# ADC.net
KiCad netlist of a schematic drawn in Altium Designer
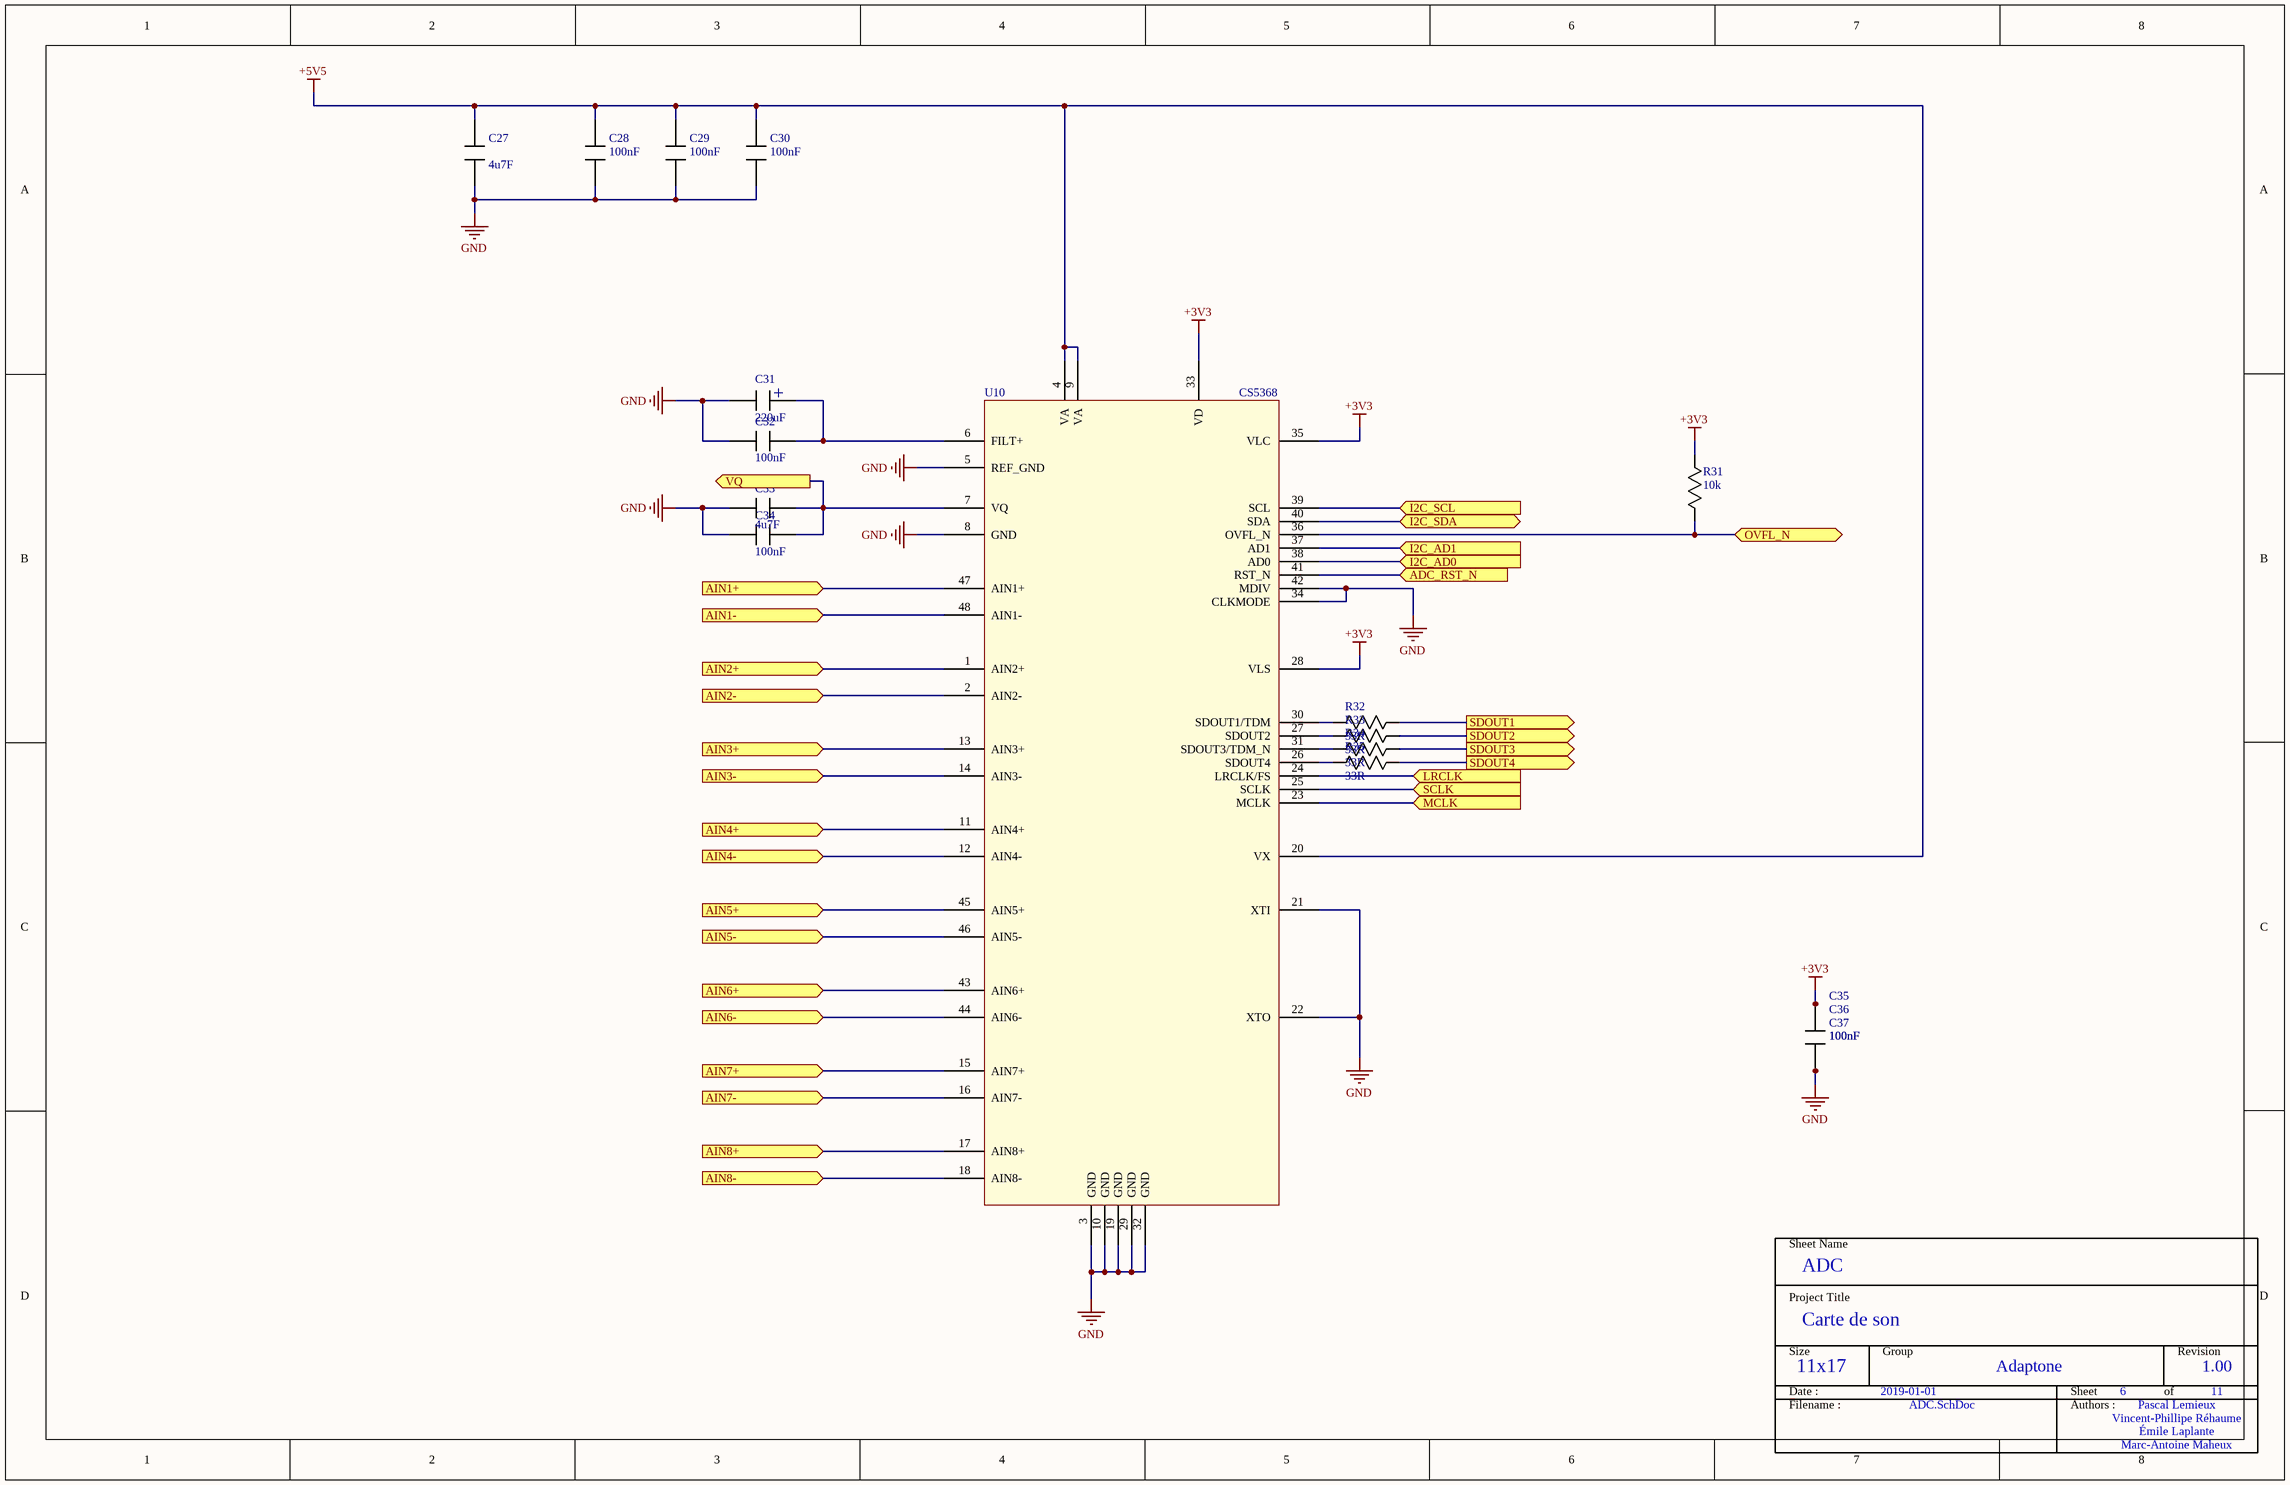
[diagram p0: ADC.SchDoc]

(export (version "E")
  (design (tool "Eeschema 10.0.6"))
  (components
    (comp (ref "C27")
      (value "4u7F")
      (footprint "0805")
      (description "Capacitor")
      (fields (field (name "MFG") "Samsung"))
      (libsource (lib "ADAPTONE_CARTE_DE_SON") (part "Capacitor"))
    )
    (comp (ref "C28")
      (value "100nF")
      (footprint "0603")
      (description "Capacitor")
      (fields (field (name "MFG") "Samsung"))
      (libsource (lib "ADAPTONE_CARTE_DE_SON") (part "Capacitor"))
    )
    (comp (ref "C29")
      (value "100nF")
      (footprint "0603")
      (description "Capacitor")
      (fields (field (name "MFG") "Samsung"))
      (libsource (lib "ADAPTONE_CARTE_DE_SON") (part "Capacitor"))
    )
    (comp (ref "C30")
      (value "100nF")
      (footprint "0603")
      (description "Capacitor")
      (fields (field (name "MFG") "Samsung"))
      (libsource (lib "ADAPTONE_CARTE_DE_SON") (part "Capacitor"))
    )
    (comp (ref "C31")
      (value "220uF")
      (footprint "CAP_RAD_SMD_DIA315")
      (description "Capacitor")
      (fields (field (name "MFG") "Nichicon") (field (name "Comment") "Capacitor_Polarized_1"))
      (libsource (lib "ADAPTONE_CARTE_DE_SON") (part "Capacitor_Polarized_1"))
    )
    (comp (ref "C32")
      (value "100nF")
      (footprint "0603")
      (description "Capacitor")
      (fields (field (name "MFG") "Samsung"))
      (libsource (lib "ADAPTONE_CARTE_DE_SON") (part "Capacitor"))
    )
    (comp (ref "C33")
      (value "4u7F")
      (footprint "0805")
      (description "Capacitor")
      (fields (field (name "MFG") "Samsung"))
      (libsource (lib "ADAPTONE_CARTE_DE_SON") (part "Capacitor"))
    )
    (comp (ref "C34")
      (value "100nF")
      (footprint "0603")
      (description "Capacitor")
      (fields (field (name "MFG") "Samsung"))
      (libsource (lib "ADAPTONE_CARTE_DE_SON") (part "Capacitor"))
    )
    (comp (ref "C35")
      (value "100nF")
      (footprint "0603")
      (description "Capacitor")
      (fields (field (name "MFG") "Samsung"))
      (libsource (lib "ADAPTONE_CARTE_DE_SON") (part "Capacitor"))
    )
    (comp (ref "C36")
      (value "100nF")
      (footprint "0603")
      (description "Capacitor")
      (fields (field (name "MFG") "Samsung"))
      (libsource (lib "ADAPTONE_CARTE_DE_SON") (part "Capacitor"))
    )
    (comp (ref "C37")
      (value "100nF")
      (footprint "0603")
      (description "Capacitor")
      (fields (field (name "MFG") "Samsung"))
      (libsource (lib "ADAPTONE_CARTE_DE_SON") (part "Capacitor"))
    )
    (comp (ref "R31")
      (value "10k")
      (footprint "0603")
      (description "Resistor")
      (fields (field (name "MFG") "Yageo"))
      (libsource (lib "ADAPTONE_CARTE_DE_SON") (part "Resistor"))
    )
    (comp (ref "R32")
      (value "33R")
      (footprint "0603")
      (description "Resistor")
      (fields (field (name "MFG") "Yageo"))
      (libsource (lib "ADAPTONE_CARTE_DE_SON") (part "Resistor"))
    )
    (comp (ref "R33")
      (value "33R")
      (footprint "0603")
      (description "Resistor")
      (fields (field (name "MFG") "Yageo"))
      (libsource (lib "ADAPTONE_CARTE_DE_SON") (part "Resistor"))
    )
    (comp (ref "R34")
      (value "33R")
      (footprint "0603")
      (description "Resistor")
      (fields (field (name "MFG") "Yageo"))
      (libsource (lib "ADAPTONE_CARTE_DE_SON") (part "Resistor"))
    )
    (comp (ref "R35")
      (value "33R")
      (footprint "0603")
      (description "Resistor")
      (fields (field (name "MFG") "Yageo"))
      (libsource (lib "ADAPTONE_CARTE_DE_SON") (part "Resistor"))
    )
    (comp (ref "U10")
      (value "CS5368")
      (footprint "LQFP_48L_CIRRUS")
      (description "ADC, 24bit, 8 chan, 192kHz, PCM, TDM, LQFP48")
      (fields (field (name "MFG") "Cirrus"))
      (libsource (lib "ADAPTONE_CARTE_DE_SON") (part "CS5368"))
    )
  )
  (nets
    (net (code "1") (name "+3V3") (class "Default")
      (node (ref "C35") (pin "1") (pintype "passive"))
      (node (ref "C36") (pin "1") (pintype "passive"))
      (node (ref "C37") (pin "1") (pintype "passive"))
      (node (ref "R31") (pin "1") (pintype "passive"))
      (node (ref "U10") (pin "28") (pinfunction "VLS_28") (pintype "passive"))
      (node (ref "U10") (pin "33") (pinfunction "VD_33") (pintype "passive"))
      (node (ref "U10") (pin "35") (pinfunction "VLC_35") (pintype "passive"))
    )
    (net (code "2") (name "+5V5") (class "Default")
      (node (ref "C27") (pin "1") (pintype "passive"))
      (node (ref "C28") (pin "1") (pintype "passive"))
      (node (ref "C29") (pin "1") (pintype "passive"))
      (node (ref "C30") (pin "1") (pintype "passive"))
      (node (ref "U10") (pin "20") (pinfunction "VX_20") (pintype "passive"))
      (node (ref "U10") (pin "4") (pinfunction "VA_4") (pintype "passive"))
      (node (ref "U10") (pin "9") (pinfunction "VA_9") (pintype "passive"))
    )
    (net (code "3") (name "/ADC_RST_N") (class "Default")
      (node (ref "U10") (pin "41") (pinfunction "RST_N_41") (pintype "passive"))
    )
    (net (code "4") (name "/AIN1+") (class "Default")
      (node (ref "U10") (pin "47") (pinfunction "AIN1+_47") (pintype "passive"))
    )
    (net (code "5") (name "/AIN1-") (class "Default")
      (node (ref "U10") (pin "48") (pinfunction "AIN1-_48") (pintype "passive"))
    )
    (net (code "6") (name "/AIN2+") (class "Default")
      (node (ref "U10") (pin "1") (pinfunction "AIN2+_1") (pintype "passive"))
    )
    (net (code "7") (name "/AIN2-") (class "Default")
      (node (ref "U10") (pin "2") (pinfunction "AIN2-_2") (pintype "passive"))
    )
    (net (code "8") (name "/AIN3+") (class "Default")
      (node (ref "U10") (pin "13") (pinfunction "AIN3+_13") (pintype "passive"))
    )
    (net (code "9") (name "/AIN3-") (class "Default")
      (node (ref "U10") (pin "14") (pinfunction "AIN3-_14") (pintype "passive"))
    )
    (net (code "10") (name "/AIN4+") (class "Default")
      (node (ref "U10") (pin "11") (pinfunction "AIN4+_11") (pintype "passive"))
    )
    (net (code "11") (name "/AIN4-") (class "Default")
      (node (ref "U10") (pin "12") (pinfunction "AIN4-_12") (pintype "passive"))
    )
    (net (code "12") (name "/AIN5+") (class "Default")
      (node (ref "U10") (pin "45") (pinfunction "AIN5+_45") (pintype "passive"))
    )
    (net (code "13") (name "/AIN5-") (class "Default")
      (node (ref "U10") (pin "46") (pinfunction "AIN5-_46") (pintype "passive"))
    )
    (net (code "14") (name "/AIN6+") (class "Default")
      (node (ref "U10") (pin "43") (pinfunction "AIN6+_43") (pintype "passive"))
    )
    (net (code "15") (name "/AIN6-") (class "Default")
      (node (ref "U10") (pin "44") (pinfunction "AIN6-_44") (pintype "passive"))
    )
    (net (code "16") (name "/AIN7+") (class "Default")
      (node (ref "U10") (pin "15") (pinfunction "AIN7+_15") (pintype "passive"))
    )
    (net (code "17") (name "/AIN7-") (class "Default")
      (node (ref "U10") (pin "16") (pinfunction "AIN7-_16") (pintype "passive"))
    )
    (net (code "18") (name "/AIN8+") (class "Default")
      (node (ref "U10") (pin "17") (pinfunction "AIN8+_17") (pintype "passive"))
    )
    (net (code "19") (name "/AIN8-") (class "Default")
      (node (ref "U10") (pin "18") (pinfunction "AIN8-_18") (pintype "passive"))
    )
    (net (code "20") (name "/I2C_AD0") (class "Default")
      (node (ref "U10") (pin "38") (pinfunction "AD0_38") (pintype "passive"))
    )
    (net (code "21") (name "/I2C_AD1") (class "Default")
      (node (ref "U10") (pin "37") (pinfunction "AD1_37") (pintype "passive"))
    )
    (net (code "22") (name "/I2C_SCL") (class "Default")
      (node (ref "U10") (pin "39") (pinfunction "SCL_39") (pintype "passive"))
    )
    (net (code "23") (name "/I2C_SDA") (class "Default")
      (node (ref "U10") (pin "40") (pinfunction "SDA_40") (pintype "passive"))
    )
    (net (code "24") (name "/LRCLK") (class "Default")
      (node (ref "U10") (pin "24") (pinfunction "LRCLK/FS_24") (pintype "passive"))
    )
    (net (code "25") (name "/MCLK") (class "Default")
      (node (ref "U10") (pin "23") (pinfunction "MCLK_23") (pintype "passive"))
    )
    (net (code "26") (name "/OVFL_N") (class "Default")
      (node (ref "R31") (pin "2") (pintype "passive"))
      (node (ref "U10") (pin "36") (pinfunction "OVFL_N_36") (pintype "passive"))
    )
    (net (code "27") (name "/SCLK") (class "Default")
      (node (ref "U10") (pin "25") (pinfunction "SCLK_25") (pintype "passive"))
    )
    (net (code "28") (name "/SDOUT1") (class "Default") (node (ref "R32") (pin "2") (pintype "passive")))
    (net (code "29") (name "/SDOUT2") (class "Default") (node (ref "R33") (pin "2") (pintype "passive")))
    (net (code "30") (name "/SDOUT3") (class "Default") (node (ref "R34") (pin "2") (pintype "passive")))
    (net (code "31") (name "/SDOUT4") (class "Default") (node (ref "R35") (pin "2") (pintype "passive")))
    (net (code "32") (name "/VQ") (class "Default")
      (node (ref "C33") (pin "1") (pintype "passive"))
      (node (ref "C34") (pin "1") (pintype "passive"))
      (node (ref "U10") (pin "7") (pinfunction "VQ_7") (pintype "passive"))
    )
    (net (code "33") (name "GND") (class "Default")
      (node (ref "C27") (pin "2") (pintype "passive"))
      (node (ref "C28") (pin "2") (pintype "passive"))
      (node (ref "C29") (pin "2") (pintype "passive"))
      (node (ref "C30") (pin "2") (pintype "passive"))
      (node (ref "C31") (pin "-") (pintype "passive"))
      (node (ref "C32") (pin "2") (pintype "passive"))
      (node (ref "C33") (pin "2") (pintype "passive"))
      (node (ref "C34") (pin "2") (pintype "passive"))
      (node (ref "C35") (pin "2") (pintype "passive"))
      (node (ref "C36") (pin "2") (pintype "passive"))
      (node (ref "C37") (pin "2") (pintype "passive"))
      (node (ref "U10") (pin "10") (pinfunction "GND_10") (pintype "passive"))
      (node (ref "U10") (pin "19") (pinfunction "GND_19") (pintype "passive"))
      (node (ref "U10") (pin "21") (pinfunction "XTI_21") (pintype "passive"))
      (node (ref "U10") (pin "22") (pinfunction "XTO_22") (pintype "passive"))
      (node (ref "U10") (pin "29") (pinfunction "GND_29") (pintype "passive"))
      (node (ref "U10") (pin "3") (pinfunction "GND_3") (pintype "passive"))
      (node (ref "U10") (pin "32") (pinfunction "GND_32") (pintype "passive"))
      (node (ref "U10") (pin "34") (pinfunction "CLKMODE_34") (pintype "passive"))
      (node (ref "U10") (pin "42") (pinfunction "MDIV_42") (pintype "passive"))
      (node (ref "U10") (pin "5") (pinfunction "REF_GND_5") (pintype "passive"))
      (node (ref "U10") (pin "8") (pinfunction "GND_8") (pintype "passive"))
    )
    (net (code "34") (name "Net-(U10-FILT+)") (class "Default")
      (node (ref "C31") (pin "+") (pintype "passive"))
      (node (ref "C32") (pin "1") (pintype "passive"))
      (node (ref "U10") (pin "6") (pinfunction "FILT+_6") (pintype "passive"))
    )
    (net (code "35") (name "Net-(U10-SDOUT1{slash}TDM)") (class "Default")
      (node (ref "R32") (pin "1") (pintype "passive"))
      (node (ref "U10") (pin "30") (pinfunction "SDOUT1/TDM_30") (pintype "passive"))
    )
    (net (code "36") (name "Net-(U10-SDOUT2)") (class "Default")
      (node (ref "R33") (pin "1") (pintype "passive"))
      (node (ref "U10") (pin "27") (pinfunction "SDOUT2_27") (pintype "passive"))
    )
    (net (code "37") (name "Net-(U10-SDOUT3{slash}TDM_N)") (class "Default")
      (node (ref "R34") (pin "1") (pintype "passive"))
      (node (ref "U10") (pin "31") (pinfunction "SDOUT3/TDM_N_31") (pintype "passive"))
    )
    (net (code "38") (name "Net-(U10-SDOUT4)") (class "Default")
      (node (ref "R35") (pin "1") (pintype "passive"))
      (node (ref "U10") (pin "26") (pinfunction "SDOUT4_26") (pintype "passive"))
    )
  )
)
